# CON_RS232DCE_DB9F.net
KiCad netlist of a schematic drawn in Altium Designer
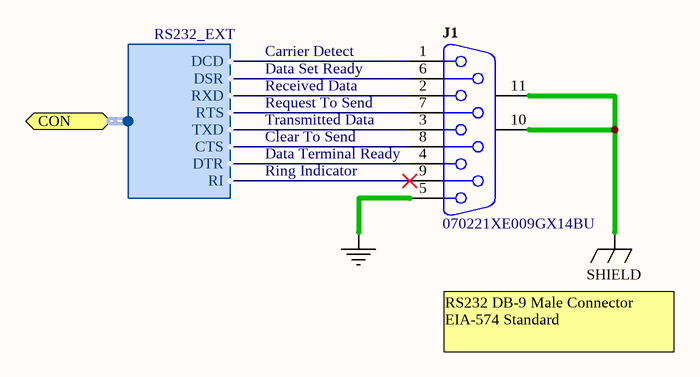
[diagram p0: CON_RS232DCE_DB9F.SchDoc]

(export (version "E")
  (design (tool "Eeschema 10.0.6"))
  (components
    (comp (ref "J1")
      (value "070221XE009GX14BU")
      (footprint "070221XE009GX14BU")
      (description "Connector DB9 SMD Male/Pins; SUYIN")
      (libsource (lib "AltiumDesignLibrary") (part "CON-DB-9-M-RA"))
    )
  )
  (nets
    (net (code "2") (name "/CTS") (class "Default")
      (node (ref "J1") (pin "8") (pinfunction "8_8") (pintype "passive"))
    )
    (net (code "3") (name "/DCD") (class "Default")
      (node (ref "J1") (pin "1") (pinfunction "1_1") (pintype "passive"))
    )
    (net (code "4") (name "/DSR") (class "Default")
      (node (ref "J1") (pin "6") (pinfunction "6_6") (pintype "passive"))
    )
    (net (code "5") (name "/DTR") (class "Default")
      (node (ref "J1") (pin "4") (pinfunction "4_4") (pintype "passive"))
    )
    (net (code "6") (name "/RI") (class "Default")
      (node (ref "J1") (pin "9") (pinfunction "9_9") (pintype "passive+no_connect"))
    )
    (net (code "7") (name "/RTS") (class "Default")
      (node (ref "J1") (pin "7") (pinfunction "7_7") (pintype "passive"))
    )
    (net (code "8") (name "/RXD") (class "Default")
      (node (ref "J1") (pin "2") (pinfunction "2_2") (pintype "passive"))
    )
    (net (code "9") (name "/TXD") (class "Default")
      (node (ref "J1") (pin "3") (pinfunction "3_3") (pintype "passive"))
    )
    (net (code "11") (name "GND") (class "Default")
      (node (ref "J1") (pin "5") (pinfunction "5_5") (pintype "passive"))
    )
    (net (code "12") (name "SHIELD") (class "Default")
      (node (ref "J1") (pin "10") (pinfunction "MH1_10") (pintype "passive"))
      (node (ref "J1") (pin "11") (pinfunction "MH2_11") (pintype "passive"))
    )
  )
)
